# power.net
KiCad netlist of a schematic drawn in Altium Designer
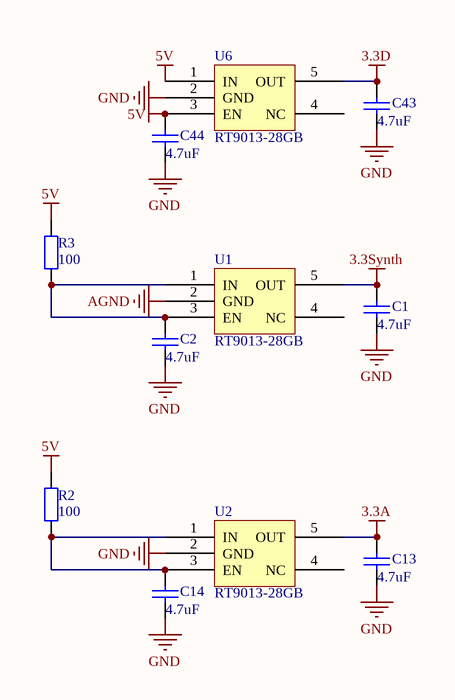
[diagram p0: power.SchDoc]

(export (version "E")
  (design (tool "Eeschema 10.0.6"))
  (components
    (comp (ref "C1")
      (value "4.7uF")
      (footprint "0603")
      (description "Capacitor")
      (fields (field (name "PUBLISHER") "Altium Limited"))
      (libsource (lib "RTC6705") (part "Cap"))
    )
    (comp (ref "C2")
      (value "4.7uF")
      (footprint "0603")
      (description "Capacitor")
      (fields (field (name "PUBLISHER") "Altium Limited"))
      (libsource (lib "RTC6705") (part "Cap"))
    )
    (comp (ref "C13")
      (value "4.7uF")
      (footprint "0603")
      (description "Capacitor")
      (fields (field (name "PUBLISHER") "Altium Limited"))
      (libsource (lib "RTC6705") (part "Cap"))
    )
    (comp (ref "C14")
      (value "4.7uF")
      (footprint "0603")
      (description "Capacitor")
      (fields (field (name "PUBLISHER") "Altium Limited"))
      (libsource (lib "RTC6705") (part "Cap"))
    )
    (comp (ref "C43")
      (value "4.7uF")
      (footprint "0603")
      (description "Capacitor")
      (fields (field (name "PUBLISHER") "Altium Limited"))
      (libsource (lib "RTC6705") (part "Cap"))
    )
    (comp (ref "C44")
      (value "4.7uF")
      (footprint "0603")
      (description "Capacitor")
      (fields (field (name "PUBLISHER") "Altium Limited"))
      (libsource (lib "RTC6705") (part "Cap"))
    )
    (comp (ref "R2")
      (value "100")
      (footprint "0603")
      (description "Resistor")
      (fields (field (name "PUBLISHER") "Altium Limited"))
      (libsource (lib "Miscellaneous Devices") (part "Res2"))
    )
    (comp (ref "R3")
      (value "100")
      (footprint "0603")
      (description "Resistor")
      (fields (field (name "PUBLISHER") "Altium Limited"))
      (libsource (lib "Miscellaneous Devices") (part "Res2"))
    )
    (comp (ref "U1") (value "RT9013-28GB") (footprint "SOT23-5") (libsource (lib "RTC6705") (part "LP5907")))
    (comp (ref "U2") (value "RT9013-28GB") (footprint "SOT23-5") (libsource (lib "RTC6705") (part "LP5907")))
    (comp (ref "U6") (value "RT9013-28GB") (footprint "SOT23-5") (libsource (lib "RTC6705") (part "LP5907")))
  )
  (nets
    (net (code "1") (name "3.3A") (class "Default")
      (node (ref "C13") (pin "2") (pinfunction "2_2") (pintype "passive"))
      (node (ref "U2") (pin "5") (pinfunction "OUT_5") (pintype "passive"))
    )
    (net (code "2") (name "3.3D") (class "Default")
      (node (ref "C43") (pin "2") (pinfunction "2_2") (pintype "passive"))
      (node (ref "U6") (pin "5") (pinfunction "OUT_5") (pintype "passive"))
    )
    (net (code "3") (name "3.3Synth") (class "Default")
      (node (ref "C1") (pin "2") (pinfunction "2_2") (pintype "passive"))
      (node (ref "U1") (pin "5") (pinfunction "OUT_5") (pintype "passive"))
    )
    (net (code "4") (name "5V") (class "Default")
      (node (ref "C44") (pin "2") (pinfunction "2_2") (pintype "passive"))
      (node (ref "R2") (pin "2") (pinfunction "2_2") (pintype "passive"))
      (node (ref "R3") (pin "2") (pinfunction "2_2") (pintype "passive"))
      (node (ref "U6") (pin "1") (pinfunction "IN_1") (pintype "passive"))
      (node (ref "U6") (pin "3") (pinfunction "EN_3") (pintype "passive"))
    )
    (net (code "5") (name "AGND") (class "Default")
      (node (ref "U1") (pin "2") (pinfunction "GND_2") (pintype "passive"))
    )
    (net (code "6") (name "GND") (class "Default")
      (node (ref "C1") (pin "1") (pinfunction "1_1") (pintype "passive"))
      (node (ref "C13") (pin "1") (pinfunction "1_1") (pintype "passive"))
      (node (ref "C14") (pin "1") (pinfunction "1_1") (pintype "passive"))
      (node (ref "C2") (pin "1") (pinfunction "1_1") (pintype "passive"))
      (node (ref "C43") (pin "1") (pinfunction "1_1") (pintype "passive"))
      (node (ref "C44") (pin "1") (pinfunction "1_1") (pintype "passive"))
      (node (ref "U2") (pin "2") (pinfunction "GND_2") (pintype "passive"))
      (node (ref "U6") (pin "2") (pinfunction "GND_2") (pintype "passive"))
    )
    (net (code "7") (name "Net-(U1-EN)") (class "Default")
      (node (ref "C2") (pin "2") (pinfunction "2_2") (pintype "passive"))
      (node (ref "R3") (pin "1") (pinfunction "1_1") (pintype "passive"))
      (node (ref "U1") (pin "1") (pinfunction "IN_1") (pintype "passive"))
      (node (ref "U1") (pin "3") (pinfunction "EN_3") (pintype "passive"))
    )
    (net (code "8") (name "Net-(U2-EN)") (class "Default")
      (node (ref "C14") (pin "2") (pinfunction "2_2") (pintype "passive"))
      (node (ref "R2") (pin "1") (pinfunction "1_1") (pintype "passive"))
      (node (ref "U2") (pin "1") (pinfunction "IN_1") (pintype "passive"))
      (node (ref "U2") (pin "3") (pinfunction "EN_3") (pintype "passive"))
    )
    (net (code "9") (name "unconnected-(U1-NC-Pad4)") (class "Default")
      (node (ref "U1") (pin "4") (pinfunction "NC_4") (pintype "passive"))
    )
    (net (code "10") (name "unconnected-(U2-NC-Pad4)") (class "Default")
      (node (ref "U2") (pin "4") (pinfunction "NC_4") (pintype "passive"))
    )
    (net (code "11") (name "unconnected-(U6-NC-Pad4)") (class "Default")
      (node (ref "U6") (pin "4") (pinfunction "NC_4") (pintype "passive"))
    )
  )
)
